# design.net
KiCad netlist of a schematic drawn in EasyEDA Pro
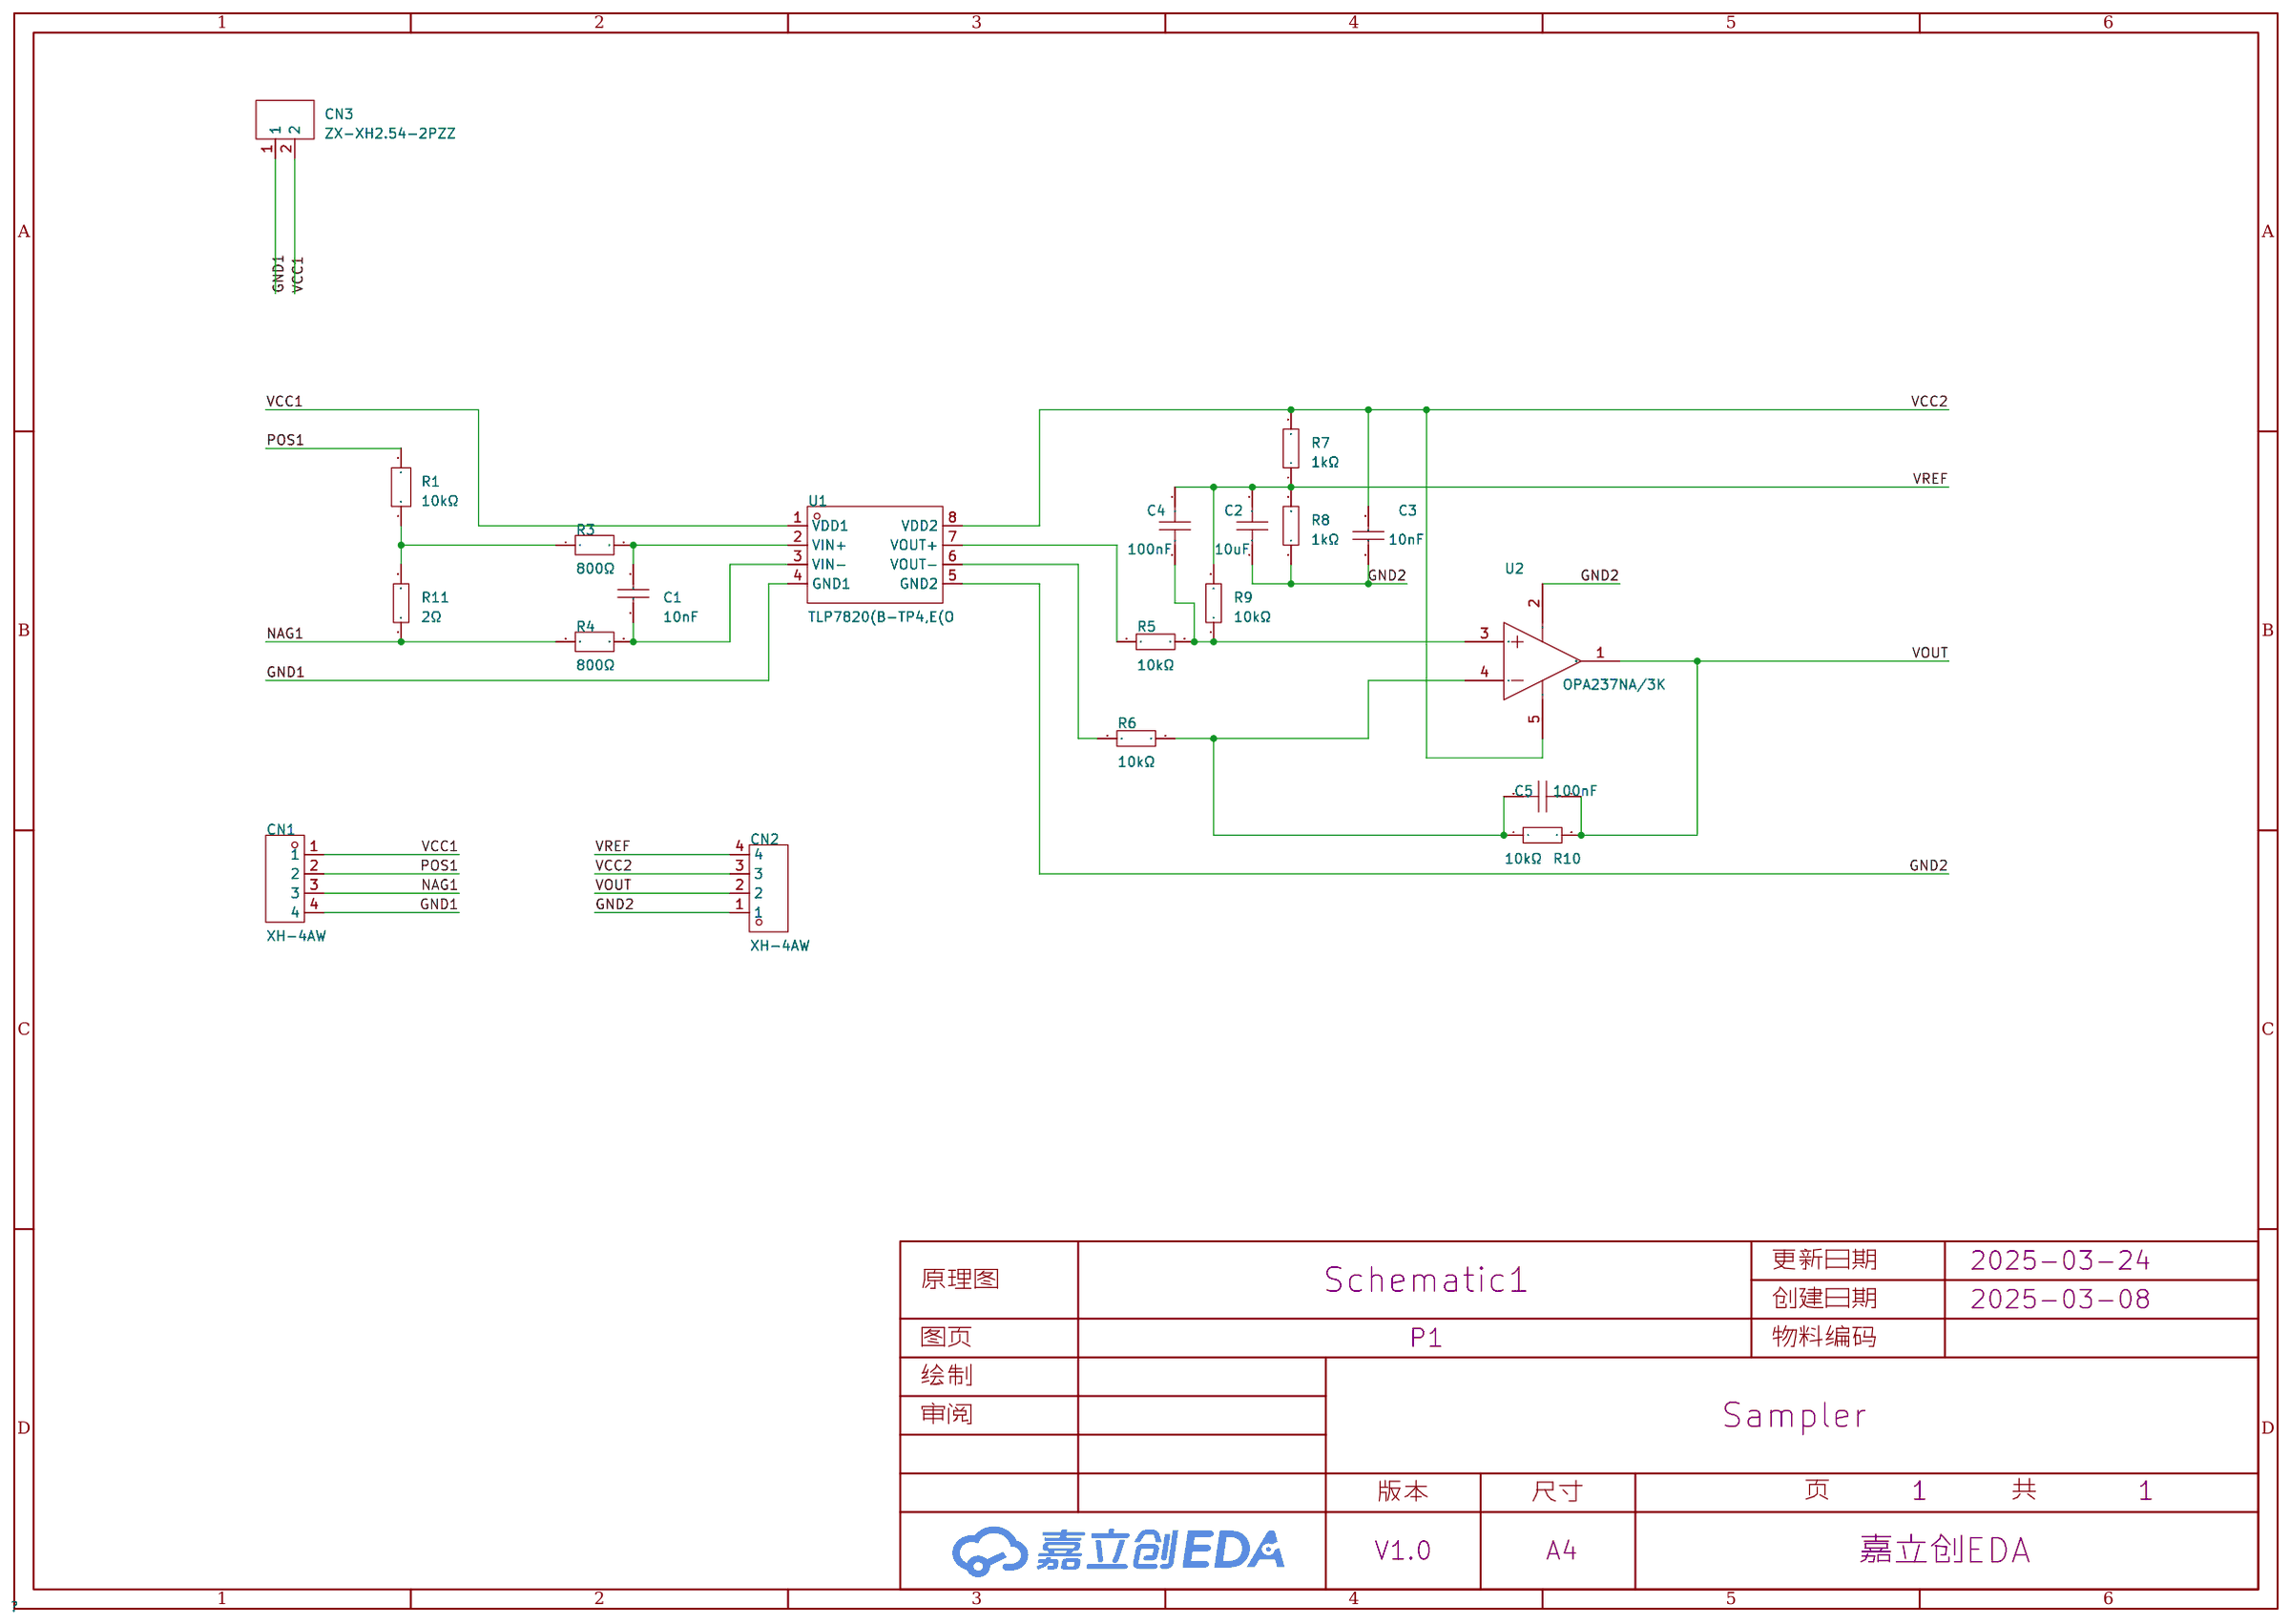
[diagram p0: schematic sheet]

(export (version "E")
  (design (tool "Eeschema 10.0.6"))
  (components
    (comp (ref "C1")
      (value "10nF")
      (footprint "easyedapro:C0805")
      (description "容值:10nF;精度:±10%;额定电压:50V;材质(温度系数):X7R;")
      (fields
        (field (name "Manufacturer Part") "CL21B103KBANNNC")
        (field (name "Manufacturer") "SAMSUNG(三星)")
      )
      (libsource (lib "easyedapro") (part "CL21B103KBANNNC"))
    )
    (comp (ref "C2")
      (value "10uF")
      (footprint "easyedapro:C0603")
      (description "容值:10uF;精度:±10%;额定电压:10V;温度系数:X5R;")
      (fields
        (field (name "Manufacturer Part") "CGA0603X5R106K100JT")
        (field (name "Manufacturer") "HRE(芯声)")
      )
      (libsource (lib "easyedapro") (part "CGA0603X5R106K100JT"))
    )
    (comp (ref "C3")
      (value "10nF")
      (footprint "easyedapro:C0603")
      (description "容值:10nF;精度:±10%;额定电压:50V;材质(温度系数):X7R;")
      (fields
        (field (name "Manufacturer Part") "CC0603KRX7R9BB103")
        (field (name "Manufacturer") "YAGEO(国巨)")
      )
      (libsource (lib "easyedapro") (part "CC0603KRX7R9BB103"))
    )
    (comp (ref "C4")
      (value "100nF")
      (footprint "easyedapro:C0603")
      (description "容值:100nF;精度:±10%;额定电压:50V;温度系数:X7R;")
      (fields
        (field (name "Manufacturer Part") "CGA0603X7R104K500JT")
        (field (name "Manufacturer") "HRE(芯声)")
      )
      (libsource (lib "easyedapro") (part "CGA0603X7R104K500JT"))
    )
    (comp (ref "C5")
      (value "100nF")
      (footprint "easyedapro:C0603")
      (description "容值:100nF;精度:±10%;额定电压:50V;温度系数:X7R;")
      (fields
        (field (name "Manufacturer Part") "CGA0603X7R104K500JT")
        (field (name "Manufacturer") "HRE(芯声)")
      )
      (libsource (lib "easyedapro") (part "CGA0603X7R104K500JT"))
    )
    (comp (ref "CN1")
      (value "XH-4AW")
      (footprint "easyedapro:CONN-TH_XH-4AW")
      (fields (field (name "Manufacturer") "HCTL(华灿天禄)"))
      (libsource (lib "easyedapro") (part "XH-4AW_C2908613"))
    )
    (comp (ref "CN2")
      (value "XH-4AW")
      (footprint "easyedapro:CONN-TH_XH-4AW")
      (fields (field (name "Manufacturer") "HCTL(华灿天禄)"))
      (libsource (lib "easyedapro") (part "XH-4AW_C2908613"))
    )
    (comp (ref "CN3")
      (value "ZX-XH2.54-2PZZ")
      (footprint "easyedapro:CONN-TH_2P-P2.50_HX25003-2A")
      (fields (field (name "Manufacturer") "Megastar(兆星)"))
      (libsource (lib "easyedapro") (part "ZX-XH2.54-2PZZ"))
    )
    (comp (ref "R1")
      (value "10kΩ")
      (footprint "easyedapro:R0805")
      (description "电阻类型:薄膜电阻;阻值:10kΩ;精度:±0.05%;功率:125mW;最大工作电压:150V;温度系数:±25ppm/°C;")
      (fields (field (name "Manufacturer Part") "RT0805WRD0710KL") (field (name "Manufacturer") "YAGEO(国巨)"))
      (libsource (lib "easyedapro") (part "RT0805WRD0710KL"))
    )
    (comp (ref "R3")
      (value "800Ω")
      (footprint "easyedapro:R0805")
      (description "电阻类型:厚膜电阻;阻值:800Ω;精度:±1%;功率:125mW;最大工作电压:150V;温度系数:±100ppm/°C;")
      (fields
        (field (name "Manufacturer Part") "0805W8F8000T5E")
        (field (name "Manufacturer") "UNI-ROYAL(厚声)")
      )
      (libsource (lib "easyedapro") (part "0805W8F8000T5E"))
    )
    (comp (ref "R4")
      (value "800Ω")
      (footprint "easyedapro:R0805")
      (description "电阻类型:厚膜电阻;阻值:800Ω;精度:±1%;功率:125mW;最大工作电压:150V;温度系数:±100ppm/°C;")
      (fields
        (field (name "Manufacturer Part") "0805W8F8000T5E")
        (field (name "Manufacturer") "UNI-ROYAL(厚声)")
      )
      (libsource (lib "easyedapro") (part "0805W8F8000T5E"))
    )
    (comp (ref "R5")
      (value "10kΩ")
      (footprint "easyedapro:R0603")
      (description "电阻类型:薄膜电阻;阻值:10kΩ;精度:±0.1%;功率:100mW;最大工作电压:75V;温度系数:±25ppm/°C;")
      (fields (field (name "Manufacturer Part") "RT0603BRD0710KL") (field (name "Manufacturer") "YAGEO(国巨)"))
      (libsource (lib "easyedapro") (part "RT0603BRD0710KL"))
    )
    (comp (ref "R6")
      (value "10kΩ")
      (footprint "easyedapro:R0603")
      (description "电阻类型:薄膜电阻;阻值:10kΩ;精度:±0.1%;功率:100mW;最大工作电压:75V;温度系数:±25ppm/°C;")
      (fields (field (name "Manufacturer Part") "RT0603BRD0710KL") (field (name "Manufacturer") "YAGEO(国巨)"))
      (libsource (lib "easyedapro") (part "RT0603BRD0710KL"))
    )
    (comp (ref "R7")
      (value "1kΩ")
      (footprint "easyedapro:R0603")
      (description "电阻类型:薄膜电阻;阻值:1kΩ;精度:±0.1%;功率:100mW;最大工作电压:75V;温度系数:±25ppm/°C;")
      (fields (field (name "Manufacturer Part") "RT0603BRD071KL") (field (name "Manufacturer") "YAGEO(国巨)"))
      (libsource (lib "easyedapro") (part "RT0603BRD071KL"))
    )
    (comp (ref "R8")
      (value "1kΩ")
      (footprint "easyedapro:R0603")
      (description "电阻类型:薄膜电阻;阻值:1kΩ;精度:±0.1%;功率:100mW;最大工作电压:75V;温度系数:±25ppm/°C;")
      (fields (field (name "Manufacturer Part") "RT0603BRD071KL") (field (name "Manufacturer") "YAGEO(国巨)"))
      (libsource (lib "easyedapro") (part "RT0603BRD071KL"))
    )
    (comp (ref "R9")
      (value "10kΩ")
      (footprint "easyedapro:R0603")
      (description "电阻类型:薄膜电阻;阻值:10kΩ;精度:±0.1%;功率:100mW;最大工作电压:75V;温度系数:±25ppm/°C;")
      (fields (field (name "Manufacturer Part") "RT0603BRD0710KL") (field (name "Manufacturer") "YAGEO(国巨)"))
      (libsource (lib "easyedapro") (part "RT0603BRD0710KL"))
    )
    (comp (ref "R10")
      (value "10kΩ")
      (footprint "easyedapro:R0603")
      (description "电阻类型:薄膜电阻;阻值:10kΩ;精度:±0.1%;功率:100mW;最大工作电压:75V;温度系数:±25ppm/°C;")
      (fields (field (name "Manufacturer Part") "RT0603BRD0710KL") (field (name "Manufacturer") "YAGEO(国巨)"))
      (libsource (lib "easyedapro") (part "RT0603BRD0710KL"))
    )
    (comp (ref "R11")
      (value "2Ω")
      (footprint "easyedapro:R0805")
      (description "电阻类型:厚膜电阻;阻值:2Ω;精度:±1%;功率:125mW;最大工作电压:150V;温度系数:±400ppm/°C;")
      (fields
        (field (name "Manufacturer Part") "0805W8F200KT5E")
        (field (name "Manufacturer") "UNI-ROYAL(厚声)")
      )
      (libsource (lib "easyedapro") (part "0805W8F200KT5E"))
    )
    (comp (ref "U1")
      (value "TLP7820(B-TP4,E(O")
      (footprint "easyedapro:SOIC-8_L5.9-W7.5-P1.27-LS11.5-BL")
      (fields (field (name "Manufacturer") "TOSHIBA(东芝)"))
      (libsource (lib "easyedapro") (part "TLP7820(B-TP4,E(O"))
    )
    (comp (ref "U2")
      (value "OPA237NA/3K")
      (footprint "easyedapro:SOT-23-5_L3.0-W1.7-P0.95-LS2.8-BR")
      (description "放大器数:单路;增益带宽积(GBP):1.5MHz;输入偏置电流(Ib):8.5nA;压摆率(SR):0.5V/us;轨到轨:-;")
      (fields (field (name "Manufacturer") "TI(德州仪器)"))
      (libsource (lib "easyedapro") (part "OPA237NA/3K"))
    )
  )
  (nets
    (net (code "1") (name "/GND1") (class "Default")
      (node (ref "CN1") (pin "4") (pinfunction "4_4") (pintype "unspecified"))
      (node (ref "CN3") (pin "1") (pinfunction "1_1") (pintype "unspecified"))
      (node (ref "U1") (pin "4") (pinfunction "GND1_4") (pintype "unspecified"))
    )
    (net (code "2") (name "/GND2") (class "Default")
      (node (ref "C2") (pin "1") (pinfunction "1_1") (pintype "unspecified"))
      (node (ref "C3") (pin "1") (pinfunction "1_1") (pintype "input"))
      (node (ref "CN2") (pin "1") (pinfunction "1_1") (pintype "unspecified"))
      (node (ref "R8") (pin "1") (pinfunction "1_1") (pintype "input"))
      (node (ref "U1") (pin "5") (pinfunction "GND2_5") (pintype "unspecified"))
      (node (ref "U2") (pin "2") (pinfunction "V-_2") (pintype "unspecified"))
    )
    (net (code "3") (name "/NAG1") (class "Default")
      (node (ref "CN1") (pin "3") (pinfunction "3_3") (pintype "unspecified"))
      (node (ref "R11") (pin "1") (pinfunction "1_1") (pintype "input"))
      (node (ref "R4") (pin "1") (pinfunction "1_1") (pintype "unspecified"))
    )
    (net (code "4") (name "/POS1") (class "Default")
      (node (ref "CN1") (pin "2") (pinfunction "2_2") (pintype "unspecified"))
      (node (ref "R1") (pin "2") (pinfunction "2_2") (pintype "unspecified"))
    )
    (net (code "5") (name "/VCC1") (class "Default")
      (node (ref "CN1") (pin "1") (pinfunction "1_1") (pintype "unspecified"))
      (node (ref "CN3") (pin "2") (pinfunction "2_2") (pintype "unspecified"))
      (node (ref "U1") (pin "1") (pinfunction "VDD1_1") (pintype "unspecified"))
    )
    (net (code "6") (name "/VCC2") (class "Default")
      (node (ref "C3") (pin "2") (pinfunction "2_2") (pintype "input"))
      (node (ref "CN2") (pin "3") (pinfunction "3_3") (pintype "unspecified"))
      (node (ref "R7") (pin "2") (pinfunction "2_2") (pintype "input"))
      (node (ref "U1") (pin "8") (pinfunction "VDD2_8") (pintype "unspecified"))
      (node (ref "U2") (pin "5") (pinfunction "V+_5") (pintype "unspecified"))
    )
    (net (code "7") (name "/VOUT") (class "Default")
      (node (ref "C5") (pin "1") (pinfunction "1_1") (pintype "unspecified"))
      (node (ref "CN2") (pin "2") (pinfunction "2_2") (pintype "unspecified"))
      (node (ref "R10") (pin "2") (pinfunction "2_2") (pintype "input"))
      (node (ref "U2") (pin "1") (pinfunction "OUT_1") (pintype "output"))
    )
    (net (code "8") (name "/VREF") (class "Default")
      (node (ref "C2") (pin "2") (pinfunction "2_2") (pintype "unspecified"))
      (node (ref "C4") (pin "2") (pinfunction "2_2") (pintype "unspecified"))
      (node (ref "CN2") (pin "4") (pinfunction "4_4") (pintype "unspecified"))
      (node (ref "R7") (pin "1") (pinfunction "1_1") (pintype "input"))
      (node (ref "R8") (pin "2") (pinfunction "2_2") (pintype "input"))
      (node (ref "R9") (pin "2") (pinfunction "2_2") (pintype "input"))
    )
    (net (code "9") (name "Net-(R1-Pad1)") (class "Default")
      (node (ref "R1") (pin "1") (pinfunction "1_1") (pintype "unspecified"))
      (node (ref "R11") (pin "2") (pinfunction "2_2") (pintype "input"))
      (node (ref "R3") (pin "1") (pinfunction "1_1") (pintype "unspecified"))
    )
    (net (code "10") (name "Net-(U1-VIN+)") (class "Default")
      (node (ref "C1") (pin "2") (pinfunction "2_2") (pintype "input"))
      (node (ref "R3") (pin "2") (pinfunction "2_2") (pintype "unspecified"))
      (node (ref "U1") (pin "2") (pinfunction "VIN+_2") (pintype "unspecified"))
    )
    (net (code "11") (name "Net-(U1-VIN-)") (class "Default")
      (node (ref "C1") (pin "1") (pinfunction "1_1") (pintype "input"))
      (node (ref "R4") (pin "2") (pinfunction "2_2") (pintype "unspecified"))
      (node (ref "U1") (pin "3") (pinfunction "VIN-_3") (pintype "unspecified"))
    )
    (net (code "12") (name "Net-(U1-VOUT+)") (class "Default")
      (node (ref "R5") (pin "1") (pinfunction "1_1") (pintype "input"))
      (node (ref "U1") (pin "7") (pinfunction "VOUT+_7") (pintype "unspecified"))
    )
    (net (code "13") (name "Net-(U1-VOUT-)") (class "Default")
      (node (ref "R6") (pin "1") (pinfunction "1_1") (pintype "input"))
      (node (ref "U1") (pin "6") (pinfunction "VOUT-_6") (pintype "unspecified"))
    )
    (net (code "14") (name "Net-(U2-IN+)") (class "Default")
      (node (ref "C4") (pin "1") (pinfunction "1_1") (pintype "unspecified"))
      (node (ref "R5") (pin "2") (pinfunction "2_2") (pintype "input"))
      (node (ref "R9") (pin "1") (pinfunction "1_1") (pintype "input"))
      (node (ref "U2") (pin "3") (pinfunction "IN+_3") (pintype "unspecified"))
    )
    (net (code "15") (name "Net-(U2-IN-)") (class "Default")
      (node (ref "C5") (pin "2") (pinfunction "2_2") (pintype "unspecified"))
      (node (ref "R10") (pin "1") (pinfunction "1_1") (pintype "input"))
      (node (ref "R6") (pin "2") (pinfunction "2_2") (pintype "input"))
      (node (ref "U2") (pin "4") (pinfunction "IN-_4") (pintype "unspecified"))
    )
  )
)
